# minidynalo.net
KiCad netlist of a schematic drawn in EAGLE
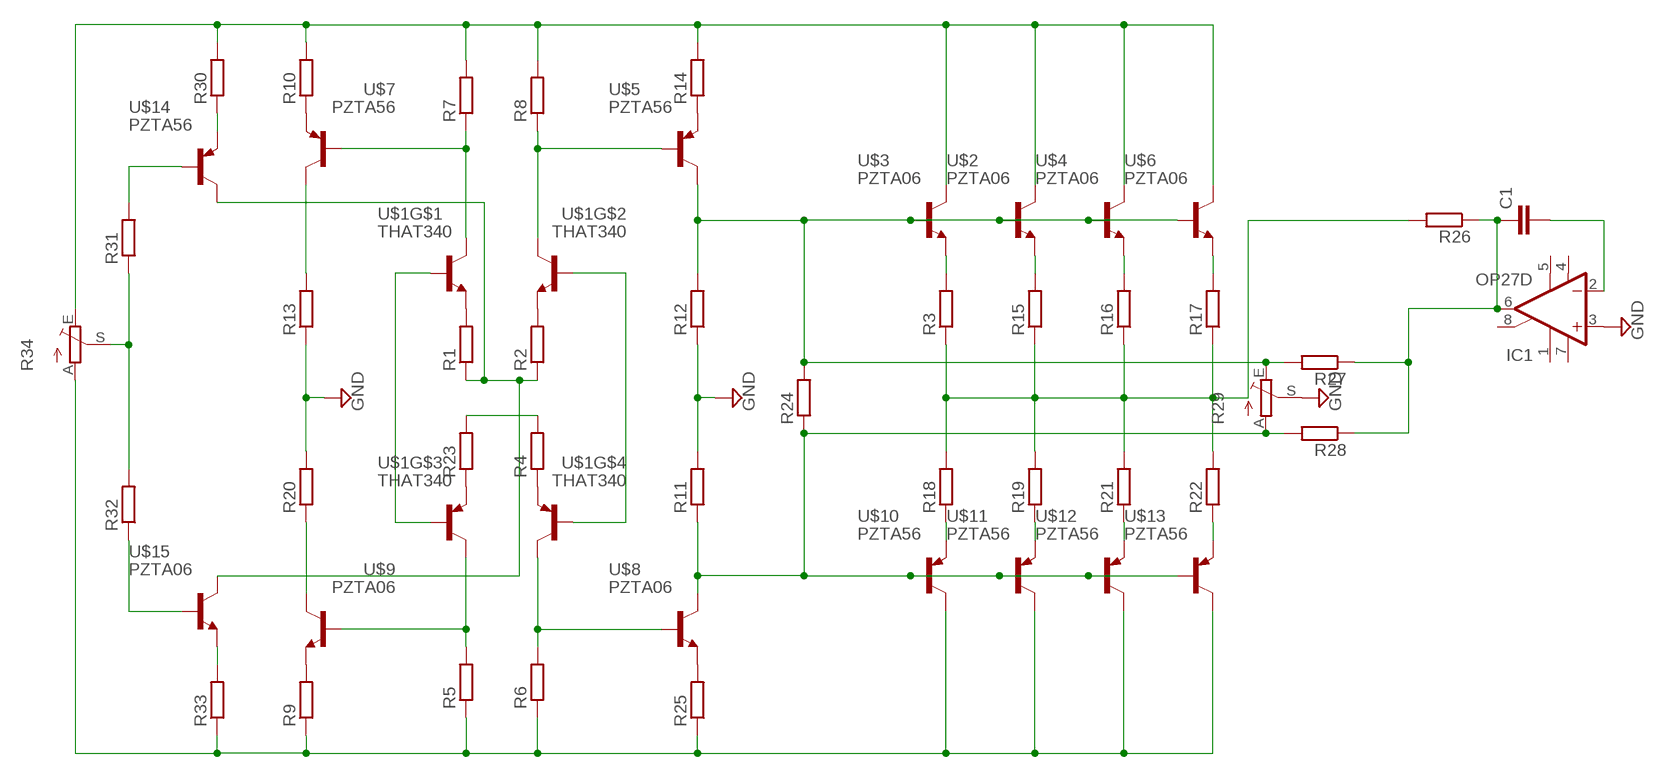
[diagram p0: schematic, sheet 1]

(export (version "E")
  (design (tool "Eeschema 10.0.6"))
  (components
    (comp (ref "C1")
      (value "C-EUC1206")
      (footprint "eagle-import:C1206")
      (libsource (lib "eagle-import") (part "C-EUC1206"))
    )
    (comp (ref "IC1")
      (value "OP27D")
      (footprint "eagle-import:SO08")
      (libsource (lib "eagle-import") (part "OP27D"))
    )
    (comp (ref "R1")
      (value "R-EU_M1206")
      (footprint "eagle-import:M1206")
      (libsource (lib "eagle-import") (part "R-EU_M1206"))
    )
    (comp (ref "R2")
      (value "R-EU_M1206")
      (footprint "eagle-import:M1206")
      (libsource (lib "eagle-import") (part "R-EU_M1206"))
    )
    (comp (ref "R3")
      (value "R-EU_M1206")
      (footprint "eagle-import:M1206")
      (libsource (lib "eagle-import") (part "R-EU_M1206"))
    )
    (comp (ref "R4")
      (value "R-EU_M1206")
      (footprint "eagle-import:M1206")
      (libsource (lib "eagle-import") (part "R-EU_M1206"))
    )
    (comp (ref "R5")
      (value "R-EU_M1206")
      (footprint "eagle-import:M1206")
      (libsource (lib "eagle-import") (part "R-EU_M1206"))
    )
    (comp (ref "R6")
      (value "R-EU_M1206")
      (footprint "eagle-import:M1206")
      (libsource (lib "eagle-import") (part "R-EU_M1206"))
    )
    (comp (ref "R7")
      (value "R-EU_M1206")
      (footprint "eagle-import:M1206")
      (libsource (lib "eagle-import") (part "R-EU_M1206"))
    )
    (comp (ref "R8")
      (value "R-EU_M1206")
      (footprint "eagle-import:M1206")
      (libsource (lib "eagle-import") (part "R-EU_M1206"))
    )
    (comp (ref "R9")
      (value "R-EU_M1206")
      (footprint "eagle-import:M1206")
      (libsource (lib "eagle-import") (part "R-EU_M1206"))
    )
    (comp (ref "R10")
      (value "R-EU_M1206")
      (footprint "eagle-import:M1206")
      (libsource (lib "eagle-import") (part "R-EU_M1206"))
    )
    (comp (ref "R11")
      (value "R-EU_M1206")
      (footprint "eagle-import:M1206")
      (libsource (lib "eagle-import") (part "R-EU_M1206"))
    )
    (comp (ref "R12")
      (value "R-EU_M1206")
      (footprint "eagle-import:M1206")
      (libsource (lib "eagle-import") (part "R-EU_M1206"))
    )
    (comp (ref "R13")
      (value "R-EU_M1206")
      (footprint "eagle-import:M1206")
      (libsource (lib "eagle-import") (part "R-EU_M1206"))
    )
    (comp (ref "R14")
      (value "R-EU_M1206")
      (footprint "eagle-import:M1206")
      (libsource (lib "eagle-import") (part "R-EU_M1206"))
    )
    (comp (ref "R15")
      (value "R-EU_M1206")
      (footprint "eagle-import:M1206")
      (libsource (lib "eagle-import") (part "R-EU_M1206"))
    )
    (comp (ref "R16")
      (value "R-EU_M1206")
      (footprint "eagle-import:M1206")
      (libsource (lib "eagle-import") (part "R-EU_M1206"))
    )
    (comp (ref "R17")
      (value "R-EU_M1206")
      (footprint "eagle-import:M1206")
      (libsource (lib "eagle-import") (part "R-EU_M1206"))
    )
    (comp (ref "R18")
      (value "R-EU_M1206")
      (footprint "eagle-import:M1206")
      (libsource (lib "eagle-import") (part "R-EU_M1206"))
    )
    (comp (ref "R19")
      (value "R-EU_M1206")
      (footprint "eagle-import:M1206")
      (libsource (lib "eagle-import") (part "R-EU_M1206"))
    )
    (comp (ref "R20")
      (value "R-EU_M1206")
      (footprint "eagle-import:M1206")
      (libsource (lib "eagle-import") (part "R-EU_M1206"))
    )
    (comp (ref "R21")
      (value "R-EU_M1206")
      (footprint "eagle-import:M1206")
      (libsource (lib "eagle-import") (part "R-EU_M1206"))
    )
    (comp (ref "R22")
      (value "R-EU_M1206")
      (footprint "eagle-import:M1206")
      (libsource (lib "eagle-import") (part "R-EU_M1206"))
    )
    (comp (ref "R23")
      (value "R-EU_M1206")
      (footprint "eagle-import:M1206")
      (libsource (lib "eagle-import") (part "R-EU_M1206"))
    )
    (comp (ref "R24")
      (value "R-EU_M1206")
      (footprint "eagle-import:M1206")
      (libsource (lib "eagle-import") (part "R-EU_M1206"))
    )
    (comp (ref "R25")
      (value "R-EU_M1206")
      (footprint "eagle-import:M1206")
      (libsource (lib "eagle-import") (part "R-EU_M1206"))
    )
    (comp (ref "R26")
      (value "R-EU_M1206")
      (footprint "eagle-import:M1206")
      (libsource (lib "eagle-import") (part "R-EU_M1206"))
    )
    (comp (ref "R27")
      (value "R-EU_M1206")
      (footprint "eagle-import:M1206")
      (libsource (lib "eagle-import") (part "R-EU_M1206"))
    )
    (comp (ref "R28")
      (value "R-EU_M1206")
      (footprint "eagle-import:M1206")
      (libsource (lib "eagle-import") (part "R-EU_M1206"))
    )
    (comp (ref "R29")
      (value "TRIM_EU-S64W")
      (footprint "eagle-import:S64W")
      (libsource (lib "eagle-import") (part "TRIM_EU-S64W"))
    )
    (comp (ref "R30")
      (value "R-EU_M1206")
      (footprint "eagle-import:M1206")
      (libsource (lib "eagle-import") (part "R-EU_M1206"))
    )
    (comp (ref "R31")
      (value "R-EU_M1206")
      (footprint "eagle-import:M1206")
      (libsource (lib "eagle-import") (part "R-EU_M1206"))
    )
    (comp (ref "R32")
      (value "R-EU_M1206")
      (footprint "eagle-import:M1206")
      (libsource (lib "eagle-import") (part "R-EU_M1206"))
    )
    (comp (ref "R33")
      (value "R-EU_M1206")
      (footprint "eagle-import:M1206")
      (libsource (lib "eagle-import") (part "R-EU_M1206"))
    )
    (comp (ref "R34")
      (value "TRIM_EU-S64W")
      (footprint "eagle-import:S64W")
      (libsource (lib "eagle-import") (part "TRIM_EU-S64W"))
    )
    (comp (ref "U$1")
      (value "THAT340")
      (footprint "eagle-import:DIP254P762X510-14")
      (libsource (lib "eagle-import") (part "THAT340"))
    )
    (comp (ref "U$2")
      (value "PZTA06")
      (footprint "eagle-import:SOT223R_INFINEON")
      (libsource (lib "eagle-import") (part "PZTA06"))
    )
    (comp (ref "U$3")
      (value "PZTA06")
      (footprint "eagle-import:SOT223R_INFINEON")
      (libsource (lib "eagle-import") (part "PZTA06"))
    )
    (comp (ref "U$4")
      (value "PZTA06")
      (footprint "eagle-import:SOT223R_INFINEON")
      (libsource (lib "eagle-import") (part "PZTA06"))
    )
    (comp (ref "U$5")
      (value "PZTA56")
      (footprint "eagle-import:SOT223R_INFINEON")
      (libsource (lib "eagle-import") (part "PZTA56"))
    )
    (comp (ref "U$6")
      (value "PZTA06")
      (footprint "eagle-import:SOT223R_INFINEON")
      (libsource (lib "eagle-import") (part "PZTA06"))
    )
    (comp (ref "U$7")
      (value "PZTA56")
      (footprint "eagle-import:SOT223R_INFINEON")
      (libsource (lib "eagle-import") (part "PZTA56"))
    )
    (comp (ref "U$8")
      (value "PZTA06")
      (footprint "eagle-import:SOT223R_INFINEON")
      (libsource (lib "eagle-import") (part "PZTA06"))
    )
    (comp (ref "U$9")
      (value "PZTA06")
      (footprint "eagle-import:SOT223R_INFINEON")
      (libsource (lib "eagle-import") (part "PZTA06"))
    )
    (comp (ref "U$10")
      (value "PZTA56")
      (footprint "eagle-import:SOT223R_INFINEON")
      (libsource (lib "eagle-import") (part "PZTA56"))
    )
    (comp (ref "U$11")
      (value "PZTA56")
      (footprint "eagle-import:SOT223R_INFINEON")
      (libsource (lib "eagle-import") (part "PZTA56"))
    )
    (comp (ref "U$12")
      (value "PZTA56")
      (footprint "eagle-import:SOT223R_INFINEON")
      (libsource (lib "eagle-import") (part "PZTA56"))
    )
    (comp (ref "U$13")
      (value "PZTA56")
      (footprint "eagle-import:SOT223R_INFINEON")
      (libsource (lib "eagle-import") (part "PZTA56"))
    )
    (comp (ref "U$14")
      (value "PZTA56")
      (footprint "eagle-import:SOT223R_INFINEON")
      (libsource (lib "eagle-import") (part "PZTA56"))
    )
    (comp (ref "U$15")
      (value "PZTA06")
      (footprint "eagle-import:SOT223R_INFINEON")
      (libsource (lib "eagle-import") (part "PZTA06"))
    )
  )
  (nets
    (net (code "1") (name "/V+") (class "Default")
      (node (ref "IC1") (pin "7") (pinfunction "V+_7") (pintype "power_in"))
    )
    (net (code "2") (name "/V-") (class "Default")
      (node (ref "IC1") (pin "4") (pinfunction "V-_4") (pintype "power_in"))
    )
    (net (code "3") (name "GND") (class "Default")
      (node (ref "IC1") (pin "3") (pinfunction "+IN_3") (pintype "input"))
      (node (ref "R11") (pin "2") (pinfunction "2_2") (pintype "passive"))
      (node (ref "R12") (pin "1") (pinfunction "1_1") (pintype "passive"))
      (node (ref "R13") (pin "1") (pinfunction "1_1") (pintype "passive"))
      (node (ref "R20") (pin "2") (pinfunction "2_2") (pintype "passive"))
      (node (ref "R29") (pin "S") (pinfunction "S_S") (pintype "passive"))
    )
    (net (code "4") (name "Net-(IC1--IN)") (class "Default")
      (node (ref "C1") (pin "2") (pinfunction "2_2") (pintype "passive"))
      (node (ref "IC1") (pin "2") (pinfunction "-IN_2") (pintype "input"))
    )
    (net (code "5") (name "Net-(IC1-OUT)") (class "Default")
      (node (ref "C1") (pin "1") (pinfunction "1_1") (pintype "passive"))
      (node (ref "IC1") (pin "6") (pinfunction "OUT_6") (pintype "output"))
      (node (ref "R26") (pin "1") (pinfunction "1_1") (pintype "passive"))
      (node (ref "R27") (pin "1") (pinfunction "1_1") (pintype "passive"))
      (node (ref "R28") (pin "1") (pinfunction "1_1") (pintype "passive"))
    )
    (net (code "6") (name "Net-(R1-Pad1)") (class "Default")
      (node (ref "R1") (pin "1") (pinfunction "1_1") (pintype "passive"))
      (node (ref "R2") (pin "1") (pinfunction "1_1") (pintype "passive"))
      (node (ref "U$14") (pin "2") (pinfunction "C_2") (pintype "passive"))
      (node (ref "U$14") (pin "4") (pinfunction "C_4") (pintype "passive"))
      (node (ref "U$15") (pin "2") (pinfunction "C_2") (pintype "passive"))
      (node (ref "U$15") (pin "4") (pinfunction "C_4") (pintype "passive"))
    )
    (net (code "7") (name "Net-(R10-Pad2)") (class "Default")
      (node (ref "R10") (pin "2") (pinfunction "2_2") (pintype "passive"))
      (node (ref "R14") (pin "2") (pinfunction "2_2") (pintype "passive"))
      (node (ref "R30") (pin "2") (pinfunction "2_2") (pintype "passive"))
      (node (ref "R34") (pin "E") (pinfunction "E_E") (pintype "passive"))
      (node (ref "R7") (pin "2") (pinfunction "2_2") (pintype "passive"))
      (node (ref "R8") (pin "2") (pinfunction "2_2") (pintype "passive"))
      (node (ref "U$2") (pin "2") (pinfunction "C_2") (pintype "passive"))
      (node (ref "U$2") (pin "4") (pinfunction "C_4") (pintype "passive"))
      (node (ref "U$3") (pin "2") (pinfunction "C_2") (pintype "passive"))
      (node (ref "U$3") (pin "4") (pinfunction "C_4") (pintype "passive"))
      (node (ref "U$4") (pin "2") (pinfunction "C_2") (pintype "passive"))
      (node (ref "U$4") (pin "4") (pinfunction "C_4") (pintype "passive"))
      (node (ref "U$6") (pin "2") (pinfunction "C_2") (pintype "passive"))
      (node (ref "U$6") (pin "4") (pinfunction "C_4") (pintype "passive"))
    )
    (net (code "8") (name "Net-(R13-Pad2)") (class "Default")
      (node (ref "R13") (pin "2") (pinfunction "2_2") (pintype "passive"))
      (node (ref "U$7") (pin "2") (pinfunction "C_2") (pintype "passive"))
      (node (ref "U$7") (pin "4") (pinfunction "C_4") (pintype "passive"))
    )
    (net (code "9") (name "Net-(R15-Pad1)") (class "Default")
      (node (ref "R15") (pin "1") (pinfunction "1_1") (pintype "passive"))
      (node (ref "R16") (pin "1") (pinfunction "1_1") (pintype "passive"))
      (node (ref "R17") (pin "1") (pinfunction "1_1") (pintype "passive"))
      (node (ref "R18") (pin "2") (pinfunction "2_2") (pintype "passive"))
      (node (ref "R19") (pin "2") (pinfunction "2_2") (pintype "passive"))
      (node (ref "R21") (pin "2") (pinfunction "2_2") (pintype "passive"))
      (node (ref "R22") (pin "2") (pinfunction "2_2") (pintype "passive"))
      (node (ref "R26") (pin "2") (pinfunction "2_2") (pintype "passive"))
      (node (ref "R3") (pin "1") (pinfunction "1_1") (pintype "passive"))
    )
    (net (code "10") (name "Net-(R20-Pad1)") (class "Default")
      (node (ref "R20") (pin "1") (pinfunction "1_1") (pintype "passive"))
      (node (ref "U$9") (pin "2") (pinfunction "C_2") (pintype "passive"))
      (node (ref "U$9") (pin "4") (pinfunction "C_4") (pintype "passive"))
    )
    (net (code "11") (name "Net-(R23-Pad2)") (class "Default")
      (node (ref "R23") (pin "2") (pinfunction "2_2") (pintype "passive"))
      (node (ref "R4") (pin "2") (pinfunction "2_2") (pintype "passive"))
    )
    (net (code "12") (name "Net-(R25-Pad1)") (class "Default")
      (node (ref "R25") (pin "1") (pinfunction "1_1") (pintype "passive"))
      (node (ref "R33") (pin "1") (pinfunction "1_1") (pintype "passive"))
      (node (ref "R34") (pin "A") (pinfunction "A_A") (pintype "passive"))
      (node (ref "R5") (pin "1") (pinfunction "1_1") (pintype "passive"))
      (node (ref "R6") (pin "1") (pinfunction "1_1") (pintype "passive"))
      (node (ref "R9") (pin "1") (pinfunction "1_1") (pintype "passive"))
      (node (ref "U$10") (pin "2") (pinfunction "C_2") (pintype "passive"))
      (node (ref "U$10") (pin "4") (pinfunction "C_4") (pintype "passive"))
      (node (ref "U$11") (pin "2") (pinfunction "C_2") (pintype "passive"))
      (node (ref "U$11") (pin "4") (pinfunction "C_4") (pintype "passive"))
      (node (ref "U$12") (pin "2") (pinfunction "C_2") (pintype "passive"))
      (node (ref "U$12") (pin "4") (pinfunction "C_4") (pintype "passive"))
      (node (ref "U$13") (pin "2") (pinfunction "C_2") (pintype "passive"))
      (node (ref "U$13") (pin "4") (pinfunction "C_4") (pintype "passive"))
    )
    (net (code "13") (name "Net-(R31-Pad1)") (class "Default")
      (node (ref "R31") (pin "1") (pinfunction "1_1") (pintype "passive"))
      (node (ref "R32") (pin "2") (pinfunction "2_2") (pintype "passive"))
      (node (ref "R34") (pin "S") (pinfunction "S_S") (pintype "passive"))
    )
    (net (code "14") (name "Net-(U$1A-B)") (class "Default")
      (node (ref "U$1") (pin "2") (pinfunction "B_2") (pintype "passive"))
      (node (ref "U$1") (pin "9") (pinfunction "B_9") (pintype "passive"))
    )
    (net (code "15") (name "Net-(U$1A-C)") (class "Default")
      (node (ref "R7") (pin "1") (pinfunction "1_1") (pintype "passive"))
      (node (ref "U$1") (pin "1") (pinfunction "C_1") (pintype "passive"))
      (node (ref "U$7") (pin "1") (pinfunction "B_1") (pintype "passive"))
    )
    (net (code "16") (name "Net-(U$1A-E)") (class "Default")
      (node (ref "R1") (pin "2") (pinfunction "2_2") (pintype "passive"))
      (node (ref "U$1") (pin "3") (pinfunction "E_3") (pintype "passive"))
    )
    (net (code "17") (name "Net-(U$1B-B)") (class "Default")
      (node (ref "U$1") (pin "13") (pinfunction "B_13") (pintype "passive"))
      (node (ref "U$1") (pin "6") (pinfunction "B_6") (pintype "passive"))
    )
    (net (code "18") (name "Net-(U$1B-C)") (class "Default")
      (node (ref "R8") (pin "1") (pinfunction "1_1") (pintype "passive"))
      (node (ref "U$1") (pin "7") (pinfunction "C_7") (pintype "passive"))
      (node (ref "U$5") (pin "1") (pinfunction "B_1") (pintype "passive"))
    )
    (net (code "19") (name "Net-(U$1B-E)") (class "Default")
      (node (ref "R2") (pin "2") (pinfunction "2_2") (pintype "passive"))
      (node (ref "U$1") (pin "5") (pinfunction "E_5") (pintype "passive"))
    )
    (net (code "20") (name "Net-(U$1C-C)") (class "Default")
      (node (ref "R5") (pin "2") (pinfunction "2_2") (pintype "passive"))
      (node (ref "U$1") (pin "8") (pinfunction "C_8") (pintype "passive"))
      (node (ref "U$9") (pin "1") (pinfunction "B_1") (pintype "passive"))
    )
    (net (code "21") (name "Net-(U$1C-E)") (class "Default")
      (node (ref "R23") (pin "1") (pinfunction "1_1") (pintype "passive"))
      (node (ref "U$1") (pin "10") (pinfunction "E_10") (pintype "passive"))
    )
    (net (code "22") (name "Net-(U$1D-C)") (class "Default")
      (node (ref "R6") (pin "2") (pinfunction "2_2") (pintype "passive"))
      (node (ref "U$1") (pin "14") (pinfunction "C_14") (pintype "passive"))
      (node (ref "U$8") (pin "1") (pinfunction "B_1") (pintype "passive"))
    )
    (net (code "23") (name "Net-(U$1D-E)") (class "Default")
      (node (ref "R4") (pin "1") (pinfunction "1_1") (pintype "passive"))
      (node (ref "U$1") (pin "12") (pinfunction "E_12") (pintype "passive"))
    )
    (net (code "24") (name "Net-(U$2-B)") (class "Default")
      (node (ref "R12") (pin "2") (pinfunction "2_2") (pintype "passive"))
      (node (ref "R24") (pin "2") (pinfunction "2_2") (pintype "passive"))
      (node (ref "R27") (pin "2") (pinfunction "2_2") (pintype "passive"))
      (node (ref "R29") (pin "E") (pinfunction "E_E") (pintype "passive"))
      (node (ref "U$2") (pin "1") (pinfunction "B_1") (pintype "passive"))
      (node (ref "U$3") (pin "1") (pinfunction "B_1") (pintype "passive"))
      (node (ref "U$4") (pin "1") (pinfunction "B_1") (pintype "passive"))
      (node (ref "U$5") (pin "2") (pinfunction "C_2") (pintype "passive"))
      (node (ref "U$5") (pin "4") (pinfunction "C_4") (pintype "passive"))
      (node (ref "U$6") (pin "1") (pinfunction "B_1") (pintype "passive"))
    )
    (net (code "25") (name "Net-(U$2-E)") (class "Default")
      (node (ref "R15") (pin "2") (pinfunction "2_2") (pintype "passive"))
      (node (ref "U$2") (pin "3") (pinfunction "E_3") (pintype "passive"))
    )
    (net (code "26") (name "Net-(U$3-E)") (class "Default")
      (node (ref "R3") (pin "2") (pinfunction "2_2") (pintype "passive"))
      (node (ref "U$3") (pin "3") (pinfunction "E_3") (pintype "passive"))
    )
    (net (code "27") (name "Net-(U$4-E)") (class "Default")
      (node (ref "R16") (pin "2") (pinfunction "2_2") (pintype "passive"))
      (node (ref "U$4") (pin "3") (pinfunction "E_3") (pintype "passive"))
    )
    (net (code "28") (name "Net-(U$5-E)") (class "Default")
      (node (ref "R14") (pin "1") (pinfunction "1_1") (pintype "passive"))
      (node (ref "U$5") (pin "3") (pinfunction "E_3") (pintype "passive"))
    )
    (net (code "29") (name "Net-(U$6-E)") (class "Default")
      (node (ref "R17") (pin "2") (pinfunction "2_2") (pintype "passive"))
      (node (ref "U$6") (pin "3") (pinfunction "E_3") (pintype "passive"))
    )
    (net (code "30") (name "Net-(U$7-E)") (class "Default")
      (node (ref "R10") (pin "1") (pinfunction "1_1") (pintype "passive"))
      (node (ref "U$7") (pin "3") (pinfunction "E_3") (pintype "passive"))
    )
    (net (code "31") (name "Net-(U$8-E)") (class "Default")
      (node (ref "R25") (pin "2") (pinfunction "2_2") (pintype "passive"))
      (node (ref "U$8") (pin "3") (pinfunction "E_3") (pintype "passive"))
    )
    (net (code "32") (name "Net-(U$9-E)") (class "Default")
      (node (ref "R9") (pin "2") (pinfunction "2_2") (pintype "passive"))
      (node (ref "U$9") (pin "3") (pinfunction "E_3") (pintype "passive"))
    )
    (net (code "33") (name "Net-(U$10-B)") (class "Default")
      (node (ref "R11") (pin "1") (pinfunction "1_1") (pintype "passive"))
      (node (ref "R24") (pin "1") (pinfunction "1_1") (pintype "passive"))
      (node (ref "R28") (pin "2") (pinfunction "2_2") (pintype "passive"))
      (node (ref "R29") (pin "A") (pinfunction "A_A") (pintype "passive"))
      (node (ref "U$10") (pin "1") (pinfunction "B_1") (pintype "passive"))
      (node (ref "U$11") (pin "1") (pinfunction "B_1") (pintype "passive"))
      (node (ref "U$12") (pin "1") (pinfunction "B_1") (pintype "passive"))
      (node (ref "U$13") (pin "1") (pinfunction "B_1") (pintype "passive"))
      (node (ref "U$8") (pin "2") (pinfunction "C_2") (pintype "passive"))
      (node (ref "U$8") (pin "4") (pinfunction "C_4") (pintype "passive"))
    )
    (net (code "34") (name "Net-(U$10-E)") (class "Default")
      (node (ref "R18") (pin "1") (pinfunction "1_1") (pintype "passive"))
      (node (ref "U$10") (pin "3") (pinfunction "E_3") (pintype "passive"))
    )
    (net (code "35") (name "Net-(U$11-E)") (class "Default")
      (node (ref "R19") (pin "1") (pinfunction "1_1") (pintype "passive"))
      (node (ref "U$11") (pin "3") (pinfunction "E_3") (pintype "passive"))
    )
    (net (code "36") (name "Net-(U$12-E)") (class "Default")
      (node (ref "R21") (pin "1") (pinfunction "1_1") (pintype "passive"))
      (node (ref "U$12") (pin "3") (pinfunction "E_3") (pintype "passive"))
    )
    (net (code "37") (name "Net-(U$13-E)") (class "Default")
      (node (ref "R22") (pin "1") (pinfunction "1_1") (pintype "passive"))
      (node (ref "U$13") (pin "3") (pinfunction "E_3") (pintype "passive"))
    )
    (net (code "38") (name "Net-(U$14-B)") (class "Default")
      (node (ref "R31") (pin "2") (pinfunction "2_2") (pintype "passive"))
      (node (ref "U$14") (pin "1") (pinfunction "B_1") (pintype "passive"))
    )
    (net (code "39") (name "Net-(U$14-E)") (class "Default")
      (node (ref "R30") (pin "1") (pinfunction "1_1") (pintype "passive"))
      (node (ref "U$14") (pin "3") (pinfunction "E_3") (pintype "passive"))
    )
    (net (code "40") (name "Net-(U$15-B)") (class "Default")
      (node (ref "R32") (pin "1") (pinfunction "1_1") (pintype "passive"))
      (node (ref "U$15") (pin "1") (pinfunction "B_1") (pintype "passive"))
    )
    (net (code "41") (name "Net-(U$15-E)") (class "Default")
      (node (ref "R33") (pin "2") (pinfunction "2_2") (pintype "passive"))
      (node (ref "U$15") (pin "3") (pinfunction "E_3") (pintype "passive"))
    )
    (net (code "42") (name "unconnected-(IC1-ON1-Pad1)") (class "Default")
      (node (ref "IC1") (pin "1") (pinfunction "ON1_1") (pintype "passive"))
    )
    (net (code "43") (name "unconnected-(IC1-ON2-Pad8)") (class "Default")
      (node (ref "IC1") (pin "8") (pinfunction "ON2_8") (pintype "passive"))
    )
    (net (code "44") (name "unconnected-(IC1-OPT-Pad5)") (class "Default")
      (node (ref "IC1") (pin "5") (pinfunction "OPT_5") (pintype "passive"))
    )
  )
)
